# Schema1.net
KiCad netlist of a schematic drawn in Altium Designer
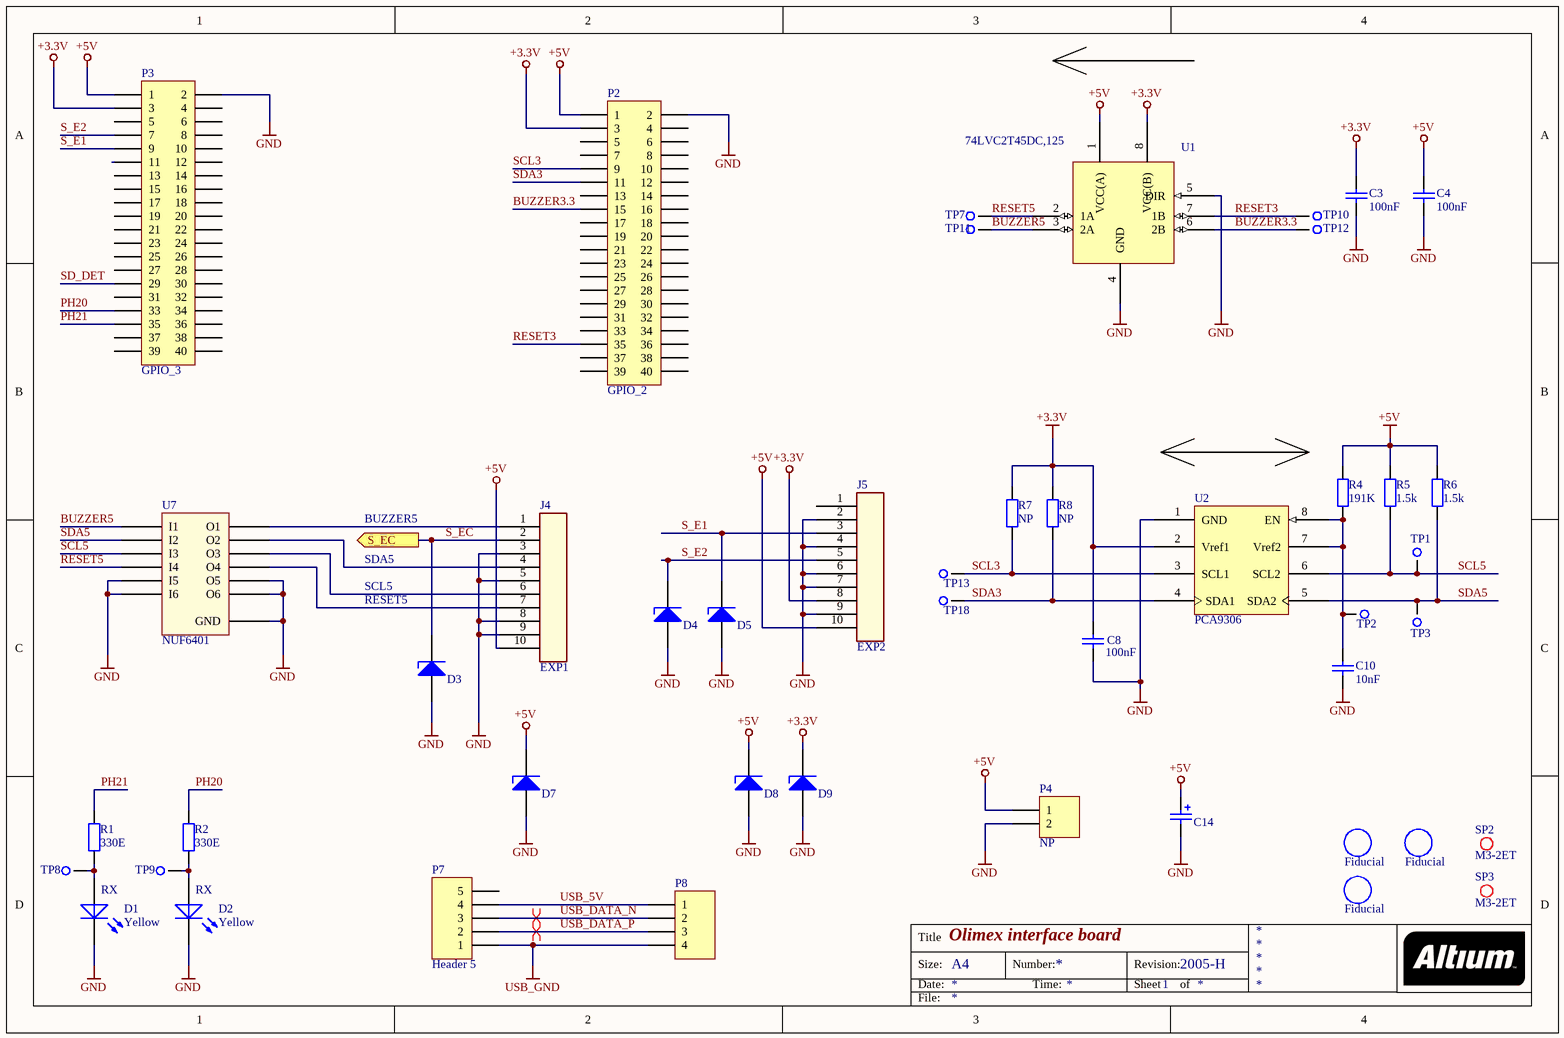
[diagram p0: Schema1.SchDoc]

(export (version "E")
  (design (tool "Eeschema 10.0.6"))
  (components
    (comp (ref "C3")
      (value "100nF")
      (footprint "C0805 (2012)")
      (description "Cap 100nF X7R 0805 10% 100V")
      (fields (field (name "MFG") "AVX"))
      (libsource (lib "Faber_SCH_lib") (part "Cap 100nF X7R 0805"))
    )
    (comp (ref "C4")
      (value "100nF")
      (footprint "C0805 (2012)")
      (description "Cap 100nF X7R 0805 10% 100V")
      (fields (field (name "MFG") "AVX"))
      (libsource (lib "Faber_SCH_lib") (part "Cap 100nF X7R 0805"))
    )
    (comp (ref "C8")
      (value "100nF")
      (footprint "C0805 (2012)")
      (description "Cap 100nF X7R 0805 10% 100V")
      (fields (field (name "MFG") "AVX"))
      (libsource (lib "Faber_SCH_lib") (part "Cap 100nF X7R 0805"))
    )
    (comp (ref "C10")
      (value "10nF")
      (footprint "C0805 (2012)")
      (description "Cap 10nF X7R 0805 10% 100V")
      (fields (field (name "MFG") "AVX"))
      (libsource (lib "Faber_SCH_lib") (part "Cap 10nF X7R 0805"))
    )
    (comp (ref "C14")
      (value "470u")
      (footprint "CAPAE7866X80M")
      (description "CAP ALUM 470UF 20% 10V SMD")
      (fields (field (name "MFG") "Panasonic Electronic Components") (field (name "TOLERANCE") "±20%"))
      (libsource (lib "Olimex interface board") (part "CAP ALUM 470UF 20% 10V SMD"))
    )
    (comp (ref "D1")
      (value "Yellow")
      (footprint "LED0805-YELLOW")
      (description "RO LED GEEL HSMY-C170 0805  AVAGO")
      (fields (field (name "MFG") "AVAGO"))
      (libsource (lib "Database_Faber") (part "LED"))
    )
    (comp (ref "D2")
      (value "Yellow")
      (footprint "LED0805-YELLOW")
      (description "RO LED GEEL HSMY-C170 0805  AVAGO")
      (fields (field (name "MFG") "AVAGO"))
      (libsource (lib "Database_Faber") (part "LED"))
    )
    (comp (ref "D3")
      (value "ESD9X3.3ST5G")
      (footprint "SODFL100X40-2N")
      (description "TVS DIODE 3.3VWM 10.4VC SOD923")
      (fields (field (name "MFG") "ON Semiconductor"))
      (libsource (lib "Olimex interface board") (part "ESD9X3.3ST5G"))
    )
    (comp (ref "D4")
      (value "ESD9X3.3ST5G")
      (footprint "SODFL100X40-2N")
      (description "TVS DIODE 3.3VWM 10.4VC SOD923")
      (fields (field (name "MFG") "ON Semiconductor"))
      (libsource (lib "Olimex interface board") (part "ESD9X3.3ST5G"))
    )
    (comp (ref "D5")
      (value "ESD9X3.3ST5G")
      (footprint "SODFL100X40-2N")
      (description "TVS DIODE 3.3VWM 10.4VC SOD923")
      (fields (field (name "MFG") "ON Semiconductor"))
      (libsource (lib "Olimex interface board") (part "ESD9X3.3ST5G"))
    )
    (comp (ref "D7")
      (value "ESD9X5.0ST5G")
      (footprint "SODFL100X40-2N")
      (description "TVS DIODE 5VWM 12.3VC SOD923")
      (fields (field (name "MFG") "ON Semiconductor"))
      (libsource (lib "Olimex interface board") (part "ESD9X5.0ST5G"))
    )
    (comp (ref "D8")
      (value "ESD9X5.0ST5G")
      (footprint "SODFL100X40-2N")
      (description "TVS DIODE 5VWM 12.3VC SOD923")
      (fields (field (name "MFG") "ON Semiconductor"))
      (libsource (lib "Olimex interface board") (part "ESD9X5.0ST5G"))
    )
    (comp (ref "D9")
      (value "ESD9X3.3ST5G")
      (footprint "SODFL100X40-2N")
      (description "TVS DIODE 3.3VWM 10.4VC SOD923")
      (fields (field (name "MFG") "ON Semiconductor"))
      (libsource (lib "Olimex interface board") (part "ESD9X3.3ST5G"))
    )
    (comp (ref "Fid1")
      (value "Fiducial")
      (footprint "Fiducial 1,5mm")
      (libsource (lib "Database_Faber") (part "Fiducial"))
    )
    (comp (ref "Fid2")
      (value "Fiducial")
      (footprint "Fiducial 1,5mm")
      (libsource (lib "Database_Faber") (part "Fiducial"))
    )
    (comp (ref "Fid3")
      (value "Fiducial")
      (footprint "Fiducial 1,5mm")
      (libsource (lib "Database_Faber") (part "Fiducial"))
    )
    (comp (ref "J4")
      (value "EXP1")
      (footprint "BOXHEADER-10P-R/A-ST-2.54")
      (description "RO CONN PR HDR BOX 10p HKS 61201021721 WUERTH")
      (libsource (lib "Database_Faber") (part "HEADER 10"))
    )
    (comp (ref "J5")
      (value "EXP2")
      (footprint "BOXHEADER-10P-R/A-ST-2.54")
      (description "RO CONN PR HDR BOX 10p HKS 61201021721 WUERTH")
      (libsource (lib "Database_Faber") (part "HEADER 10"))
    )
    (comp (ref "P2")
      (value "GPIO_2")
      (footprint "M50-3152042")
      (description "HARWIN - M50-3152042 - SOCKET, DUAL ENTRY, SMT, 40WAY")
      (fields (field (name "MFG") "Harwin") (field (name "PUBLISHER") "Altium Limited"))
      (libsource (lib "Miscellaneous Connectors") (part "MHDR2X20"))
    )
    (comp (ref "P3")
      (value "GPIO_3")
      (footprint "M50-3152042")
      (description "HARWIN - M50-3152042 - SOCKET, DUAL ENTRY, SMT, 40WAY")
      (fields (field (name "MFG") "Harwin") (field (name "PUBLISHER") "Altium Limited"))
      (libsource (lib "Miscellaneous Connectors") (part "MHDR2X20"))
    )
    (comp (ref "P4")
      (value "NP")
      (footprint "HDR1X2")
      (fields (field (name "PUBLISHER") "Altium Limited"))
      (libsource (lib "Miscellaneous Connectors") (part "Header 2"))
    )
    (comp (ref "P7")
      (value "Header 5")
      (footprint "Female Header 5 pins")
      (description "Header, 5-Pin")
      (fields (field (name "MFG") "Multicomp"))
      (libsource (lib "Miscellaneous Connectors") (part "Header 5"))
    )
    (comp (ref "P8")
      (value "~")
      (footprint "B4B-XH-A")
      (description "Header, 4-Pin")
      (fields
        (field (name "MFG") "JST (JAPAN SOLDERLESS TERMINALS)")
        (field (name "PUBLISHER") "Altium Limited")
      )
      (libsource (lib "Miscellaneous Connectors") (part "Header 4"))
    )
    (comp (ref "R1")
      (value "330E")
      (footprint "RESC1608X05N")
      (description "RES 330 OHM 1/10W 1% 0603 SMD")
      (fields
        (field (name "MANUFACTURER") "Vishay Dale")
        (field (name "MANUFACTURER PART NUMBER") "CRCW0603330RFKEA")
      )
      (libsource (lib "Marlin") (part "330E/0603"))
    )
    (comp (ref "R2")
      (value "330E")
      (footprint "RESC1608X05N")
      (description "RES 330 OHM 1/10W 1% 0603 SMD")
      (fields
        (field (name "MANUFACTURER") "Vishay Dale")
        (field (name "MANUFACTURER PART NUMBER") "CRCW0603330RFKEA")
      )
      (libsource (lib "Marlin") (part "330E/0603"))
    )
    (comp (ref "R4")
      (value "191K")
      (footprint "R0805 (2012)")
      (description "Res 191K 0805 1% 125mW")
      (fields (field (name "MFG") "VISHAY DRALORIC"))
      (libsource (lib "Faber_SCH_lib") (part "Res 191K 0805"))
    )
    (comp (ref "R5")
      (value "1.5k")
      (footprint "RESC1608X05N")
      (description "RES SMD 1.5K OHM 1% 1/10W 0603")
      (fields
        (field (name "MANUFACTURER") "Vishay Dale")
        (field (name "MANUFACTURER PART NUMBER") "CRCW06031K50FKEA")
      )
      (libsource (lib "Olimex interface board") (part "47k/0603"))
    )
    (comp (ref "R6")
      (value "1.5k")
      (footprint "RESC1608X05N")
      (description "RES SMD 1.5K OHM 1% 1/10W 0603")
      (fields
        (field (name "MANUFACTURER") "Vishay Dale")
        (field (name "MANUFACTURER PART NUMBER") "CRCW06031K50FKEA")
      )
      (libsource (lib "Olimex interface board") (part "47k/0603"))
    )
    (comp (ref "R7")
      (value "NP")
      (footprint "R0805 (2012)")
      (description "Res 4.7K 0805 1% 100mW")
      (fields (field (name "MFG") "MULTICOMP"))
      (libsource (lib "Faber_SCH_lib") (part "Res 4.7K 0805"))
    )
    (comp (ref "R8")
      (value "NP")
      (footprint "R0805 (2012)")
      (description "Res 4.7K 0805 1% 100mW")
      (fields (field (name "MFG") "MULTICOMP"))
      (libsource (lib "Faber_SCH_lib") (part "Res 4.7K 0805"))
    )
    (comp (ref "SP2")
      (value "M3-2ET")
      (footprint "SPACER M3-4ET")
      (description "MOER-SMD SMTSO-M3-2ET  PEM")
      (fields (field (name "MFG") "PEM"))
      (libsource (lib "Faber_SCH_lib") (part "Spacer M3-10ET"))
    )
    (comp (ref "SP3")
      (value "M3-2ET")
      (footprint "Spacer M3-4ETkleinepad")
      (description "MOER-SMD SMTSO-M3-2ET  PEM")
      (fields (field (name "MFG") "PEM"))
      (libsource (lib "Faber_SCH_lib") (part "Spacer M3-10ET"))
    )
    (comp (ref "TP1")
      (value "2mm")
      (footprint "TESTPOINT 2mm")
      (description "Testpoint, 2mm, round")
      (libsource (lib "Faber_SCH_lib") (part "Testpoint, 2mm, round"))
    )
    (comp (ref "TP2")
      (value "2mm")
      (footprint "TESTPOINT 2mm")
      (description "Testpoint, 2mm, round")
      (libsource (lib "Faber_SCH_lib") (part "Testpoint, 2mm, round"))
    )
    (comp (ref "TP3")
      (value "2mm")
      (footprint "TESTPOINT 2mm")
      (description "Testpoint, 2mm, round")
      (libsource (lib "Faber_SCH_lib") (part "Testpoint, 2mm, round"))
    )
    (comp (ref "TP7")
      (value "2mm")
      (footprint "TESTPOINT 2mm")
      (description "Testpoint, 2mm, round")
      (libsource (lib "Faber_SCH_lib") (part "Testpoint, 2mm, round"))
    )
    (comp (ref "TP8")
      (value "2mm")
      (footprint "TESTPOINT 2mm")
      (description "Testpoint, 2mm, round")
      (libsource (lib "Faber_SCH_lib") (part "Testpoint, 2mm, round"))
    )
    (comp (ref "TP9")
      (value "2mm")
      (footprint "TESTPOINT 2mm")
      (description "Testpoint, 2mm, round")
      (libsource (lib "Faber_SCH_lib") (part "Testpoint, 2mm, round"))
    )
    (comp (ref "TP10")
      (value "2mm")
      (footprint "TESTPOINT 2mm")
      (description "Testpoint, 2mm, round")
      (libsource (lib "Faber_SCH_lib") (part "Testpoint, 2mm, round"))
    )
    (comp (ref "TP11")
      (value "2mm")
      (footprint "TESTPOINT 2mm")
      (description "Testpoint, 2mm, round")
      (libsource (lib "Faber_SCH_lib") (part "Testpoint, 2mm, round"))
    )
    (comp (ref "TP12")
      (value "2mm")
      (footprint "TESTPOINT 2mm")
      (description "Testpoint, 2mm, round")
      (libsource (lib "Faber_SCH_lib") (part "Testpoint, 2mm, round"))
    )
    (comp (ref "TP13")
      (value "2mm")
      (footprint "TESTPOINT 2mm")
      (description "Testpoint, 2mm, round")
      (libsource (lib "Faber_SCH_lib") (part "Testpoint, 2mm, round"))
    )
    (comp (ref "TP18")
      (value "2mm")
      (footprint "TESTPOINT 2mm")
      (description "Testpoint, 2mm, round")
      (libsource (lib "Faber_SCH_lib") (part "Testpoint, 2mm, round"))
    )
    (comp (ref "U1")
      (value "74LVC2T45DC,125")
      (footprint "TSSOP50P310X100-8N")
      (description "2-bit translaing transceiver")
      (fields (field (name "MFG") "NXP"))
      (libsource (lib "Olimex interface board") (part "74LVC2T45DC,125"))
    )
    (comp (ref "U2")
      (value "PCA9306")
      (footprint "IC SSOP-8")
      (description "IC PCA9306 Voltage Level translator")
      (fields (field (name "MFG") "TEXAS INSTRUMENTS"))
      (libsource (lib "Faber_SCH_lib") (part "IC PCA9306"))
    )
    (comp (ref "U7")
      (value "NUF6401")
      (footprint "SON50P140X100_HS-13N")
      (fields (field (name "MFG") "ON Semiconductor"))
      (libsource (lib "UltiController") (part "NUF6401"))
    )
  )
  (nets
    (net (code "1") (name "+3.3V") (class "Default")
      (node (ref "C3") (pin "1") (pinfunction "1_1") (pintype "passive"))
      (node (ref "C8") (pin "2") (pinfunction "2_2") (pintype "passive"))
      (node (ref "D9") (pin "1") (pinfunction "K_1") (pintype "passive"))
      (node (ref "J5") (pin "8") (pinfunction "8_8") (pintype "passive"))
      (node (ref "P2") (pin "3") (pinfunction "3_3") (pintype "passive"))
      (node (ref "P3") (pin "3") (pinfunction "3_3") (pintype "passive"))
      (node (ref "R7") (pin "2") (pinfunction "2_2") (pintype "passive"))
      (node (ref "R8") (pin "2") (pinfunction "2_2") (pintype "passive"))
      (node (ref "U1") (pin "8") (pinfunction "VCC(B)_8") (pintype "power_in"))
      (node (ref "U2") (pin "2") (pinfunction "Vref1_2") (pintype "power_in"))
    )
    (net (code "2") (name "+5V") (class "Default")
      (node (ref "C14") (pin "1") (pinfunction "1_1") (pintype "passive"))
      (node (ref "C4") (pin "1") (pinfunction "1_1") (pintype "passive"))
      (node (ref "D7") (pin "1") (pinfunction "K_1") (pintype "passive"))
      (node (ref "D8") (pin "1") (pinfunction "K_1") (pintype "passive"))
      (node (ref "J4") (pin "10") (pinfunction "10_10") (pintype "passive"))
      (node (ref "J5") (pin "10") (pinfunction "10_10") (pintype "passive"))
      (node (ref "P2") (pin "1") (pinfunction "1_1") (pintype "passive"))
      (node (ref "P3") (pin "1") (pinfunction "1_1") (pintype "passive"))
      (node (ref "P4") (pin "1") (pinfunction "1_1") (pintype "passive"))
      (node (ref "R4") (pin "2") (pinfunction "2_2") (pintype "passive"))
      (node (ref "R5") (pin "2") (pinfunction "2_2") (pintype "passive"))
      (node (ref "R6") (pin "2") (pinfunction "2_2") (pintype "passive"))
      (node (ref "U1") (pin "1") (pinfunction "VCC(A)_1") (pintype "power_in"))
    )
    (net (code "3") (name "/BUZZER3.3") (class "Default")
      (node (ref "P2") (pin "15") (pinfunction "15_15") (pintype "passive"))
      (node (ref "TP12") (pin "1") (pinfunction "1_1") (pintype "passive"))
      (node (ref "U1") (pin "6") (pinfunction "2B_6") (pintype "bidirectional"))
    )
    (net (code "4") (name "/BUZZER5") (class "Default")
      (node (ref "TP11") (pin "1") (pinfunction "1_1") (pintype "passive"))
      (node (ref "U1") (pin "3") (pinfunction "2A_3") (pintype "bidirectional"))
      (node (ref "U7") (pin "1") (pinfunction "I1_1") (pintype "passive"))
    )
    (net (code "5") (name "/PH20") (class "Default")
      (node (ref "P3") (pin "33") (pinfunction "33_33") (pintype "passive"))
      (node (ref "R2") (pin "2") (pinfunction "2_2") (pintype "passive"))
    )
    (net (code "6") (name "/PH21") (class "Default")
      (node (ref "P3") (pin "35") (pinfunction "35_35") (pintype "passive"))
      (node (ref "R1") (pin "2") (pinfunction "2_2") (pintype "passive"))
    )
    (net (code "7") (name "/RESET3") (class "Default")
      (node (ref "P2") (pin "35") (pinfunction "35_35") (pintype "passive"))
      (node (ref "TP10") (pin "1") (pinfunction "1_1") (pintype "passive"))
      (node (ref "U1") (pin "7") (pinfunction "1B_7") (pintype "bidirectional"))
    )
    (net (code "8") (name "/RESET5") (class "Default")
      (node (ref "TP7") (pin "1") (pinfunction "1_1") (pintype "passive"))
      (node (ref "U1") (pin "2") (pinfunction "1A_2") (pintype "bidirectional"))
      (node (ref "U7") (pin "4") (pinfunction "I4_4") (pintype "passive"))
    )
    (net (code "9") (name "/SCL3") (class "Default")
      (node (ref "P2") (pin "9") (pinfunction "9_9") (pintype "passive"))
      (node (ref "R7") (pin "1") (pinfunction "1_1") (pintype "passive"))
      (node (ref "TP13") (pin "1") (pinfunction "1_1") (pintype "passive"))
      (node (ref "U2") (pin "3") (pinfunction "SCL1_3") (pintype "passive"))
    )
    (net (code "10") (name "/SCL5") (class "Default")
      (node (ref "R5") (pin "1") (pinfunction "1_1") (pintype "passive"))
      (node (ref "TP1") (pin "1") (pinfunction "1_1") (pintype "passive"))
      (node (ref "U2") (pin "6") (pinfunction "SCL2_6") (pintype "passive"))
      (node (ref "U7") (pin "3") (pinfunction "I3_3") (pintype "passive"))
    )
    (net (code "11") (name "/SDA3") (class "Default")
      (node (ref "P2") (pin "11") (pinfunction "11_11") (pintype "passive"))
      (node (ref "R8") (pin "1") (pinfunction "1_1") (pintype "passive"))
      (node (ref "TP18") (pin "1") (pinfunction "1_1") (pintype "passive"))
      (node (ref "U2") (pin "4") (pinfunction "SDA1_4") (pintype "passive"))
    )
    (net (code "12") (name "/SDA5") (class "Default")
      (node (ref "R6") (pin "1") (pinfunction "1_1") (pintype "passive"))
      (node (ref "TP3") (pin "1") (pinfunction "1_1") (pintype "passive"))
      (node (ref "U2") (pin "5") (pinfunction "SDA2_5") (pintype "passive"))
      (node (ref "U7") (pin "2") (pinfunction "I2_2") (pintype "passive"))
    )
    (net (code "13") (name "/SD_DET") (class "Default")
      (node (ref "P3") (pin "29") (pinfunction "29_29") (pintype "passive"))
    )
    (net (code "14") (name "/S_E1") (class "Default")
      (node (ref "D5") (pin "1") (pinfunction "K_1") (pintype "passive"))
      (node (ref "J5") (pin "3") (pinfunction "3_3") (pintype "passive"))
      (node (ref "P3") (pin "9") (pinfunction "9_9") (pintype "passive"))
    )
    (net (code "15") (name "/S_E2") (class "Default")
      (node (ref "D4") (pin "1") (pinfunction "K_1") (pintype "passive"))
      (node (ref "J5") (pin "5") (pinfunction "5_5") (pintype "passive"))
      (node (ref "P3") (pin "7") (pinfunction "7_7") (pintype "passive"))
    )
    (net (code "16") (name "/S_EC") (class "Default")
      (node (ref "D3") (pin "1") (pinfunction "K_1") (pintype "passive"))
      (node (ref "J4") (pin "2") (pinfunction "2_2") (pintype "passive"))
    )
    (net (code "17") (name "/USB_5V") (class "Default")
      (node (ref "P7") (pin "4") (pinfunction "4_4") (pintype "passive"))
      (node (ref "P8") (pin "1") (pinfunction "1_1") (pintype "passive"))
    )
    (net (code "18") (name "/USB_DATA_N") (class "Default")
      (node (ref "P7") (pin "3") (pinfunction "3_3") (pintype "passive"))
      (node (ref "P8") (pin "2") (pinfunction "2_2") (pintype "passive"))
    )
    (net (code "19") (name "/USB_DATA_P") (class "Default")
      (node (ref "P7") (pin "2") (pinfunction "2_2") (pintype "passive"))
      (node (ref "P8") (pin "3") (pinfunction "3_3") (pintype "passive"))
    )
    (net (code "20") (name "GND") (class "Default")
      (node (ref "C10") (pin "1") (pinfunction "1_1") (pintype "passive"))
      (node (ref "C14") (pin "2") (pinfunction "2_2") (pintype "passive"))
      (node (ref "C3") (pin "2") (pinfunction "2_2") (pintype "passive"))
      (node (ref "C4") (pin "2") (pinfunction "2_2") (pintype "passive"))
      (node (ref "C8") (pin "1") (pinfunction "1_1") (pintype "passive"))
      (node (ref "D1") (pin "2") (pinfunction "K_2") (pintype "passive"))
      (node (ref "D2") (pin "2") (pinfunction "K_2") (pintype "passive"))
      (node (ref "D3") (pin "2") (pinfunction "A_2") (pintype "passive"))
      (node (ref "D4") (pin "2") (pinfunction "A_2") (pintype "passive"))
      (node (ref "D5") (pin "2") (pinfunction "A_2") (pintype "passive"))
      (node (ref "D7") (pin "2") (pinfunction "A_2") (pintype "passive"))
      (node (ref "D8") (pin "2") (pinfunction "A_2") (pintype "passive"))
      (node (ref "D9") (pin "2") (pinfunction "A_2") (pintype "passive"))
      (node (ref "J4") (pin "3") (pinfunction "3_3") (pintype "passive"))
      (node (ref "J4") (pin "5") (pinfunction "5_5") (pintype "passive"))
      (node (ref "J4") (pin "8") (pinfunction "8_8") (pintype "passive"))
      (node (ref "J4") (pin "9") (pinfunction "9_9") (pintype "passive"))
      (node (ref "J5") (pin "2") (pinfunction "2_2") (pintype "passive"))
      (node (ref "J5") (pin "4") (pinfunction "4_4") (pintype "passive"))
      (node (ref "J5") (pin "6") (pinfunction "6_6") (pintype "passive"))
      (node (ref "J5") (pin "7") (pinfunction "7_7") (pintype "passive"))
      (node (ref "J5") (pin "9") (pinfunction "9_9") (pintype "passive"))
      (node (ref "P2") (pin "2") (pinfunction "2_2") (pintype "passive"))
      (node (ref "P3") (pin "2") (pinfunction "2_2") (pintype "passive"))
      (node (ref "P4") (pin "2") (pinfunction "2_2") (pintype "passive"))
      (node (ref "U1") (pin "4") (pinfunction "GND_4") (pintype "power_in"))
      (node (ref "U1") (pin "5") (pinfunction "DIR_5") (pintype "input"))
      (node (ref "U2") (pin "1") (pinfunction "GND_1") (pintype "power_in"))
      (node (ref "U7") (pin "13") (pinfunction "GND_13") (pintype "passive"))
      (node (ref "U7") (pin "5") (pinfunction "I5_5") (pintype "passive"))
      (node (ref "U7") (pin "6") (pinfunction "I6_6") (pintype "passive"))
      (node (ref "U7") (pin "7") (pinfunction "O6_7") (pintype "passive"))
      (node (ref "U7") (pin "8") (pinfunction "O5_8") (pintype "passive"))
    )
    (net (code "21") (name "Net-(D1-A)") (class "Default")
      (node (ref "D1") (pin "1") (pinfunction "A_1") (pintype "passive"))
      (node (ref "R1") (pin "1") (pinfunction "1_1") (pintype "passive"))
      (node (ref "TP8") (pin "1") (pinfunction "1_1") (pintype "passive"))
    )
    (net (code "22") (name "Net-(D2-A)") (class "Default")
      (node (ref "D2") (pin "1") (pinfunction "A_1") (pintype "passive"))
      (node (ref "R2") (pin "1") (pinfunction "1_1") (pintype "passive"))
      (node (ref "TP9") (pin "1") (pinfunction "1_1") (pintype "passive"))
    )
    (net (code "23") (name "Net-(U2-EN)") (class "Default")
      (node (ref "C10") (pin "2") (pinfunction "2_2") (pintype "passive"))
      (node (ref "R4") (pin "1") (pinfunction "1_1") (pintype "passive"))
      (node (ref "TP2") (pin "1") (pinfunction "1_1") (pintype "passive"))
      (node (ref "U2") (pin "7") (pinfunction "Vref2_7") (pintype "power_in"))
      (node (ref "U2") (pin "8") (pinfunction "EN_8") (pintype "input"))
    )
    (net (code "24") (name "Net-(U7-O1)") (class "Default")
      (node (ref "J4") (pin "1") (pinfunction "1_1") (pintype "passive"))
      (node (ref "U7") (pin "12") (pinfunction "O1_12") (pintype "passive"))
    )
    (net (code "25") (name "Net-(U7-O2)") (class "Default")
      (node (ref "J4") (pin "4") (pinfunction "4_4") (pintype "passive"))
      (node (ref "U7") (pin "11") (pinfunction "O2_11") (pintype "passive"))
    )
    (net (code "26") (name "Net-(U7-O3)") (class "Default")
      (node (ref "J4") (pin "6") (pinfunction "6_6") (pintype "passive"))
      (node (ref "U7") (pin "10") (pinfunction "O3_10") (pintype "passive"))
    )
    (net (code "27") (name "Net-(U7-O4)") (class "Default")
      (node (ref "J4") (pin "7") (pinfunction "7_7") (pintype "passive"))
      (node (ref "U7") (pin "9") (pinfunction "O4_9") (pintype "passive"))
    )
    (net (code "28") (name "USB_GND") (class "Default")
      (node (ref "P7") (pin "1") (pinfunction "1_1") (pintype "passive"))
      (node (ref "P8") (pin "4") (pinfunction "4_4") (pintype "passive"))
    )
    (net (code "29") (name "unconnected-(J5-Pad1)") (class "Default")
      (node (ref "J5") (pin "1") (pinfunction "1_1") (pintype "passive"))
    )
    (net (code "30") (name "unconnected-(P2-Pad4)") (class "Default")
      (node (ref "P2") (pin "4") (pinfunction "4_4") (pintype "passive"))
    )
    (net (code "31") (name "unconnected-(P2-Pad5)") (class "Default")
      (node (ref "P2") (pin "5") (pinfunction "5_5") (pintype "passive"))
    )
    (net (code "32") (name "unconnected-(P2-Pad6)") (class "Default")
      (node (ref "P2") (pin "6") (pinfunction "6_6") (pintype "passive"))
    )
    (net (code "33") (name "unconnected-(P2-Pad7)") (class "Default")
      (node (ref "P2") (pin "7") (pinfunction "7_7") (pintype "passive"))
    )
    (net (code "34") (name "unconnected-(P2-Pad8)") (class "Default")
      (node (ref "P2") (pin "8") (pinfunction "8_8") (pintype "passive"))
    )
    (net (code "35") (name "unconnected-(P2-Pad10)") (class "Default")
      (node (ref "P2") (pin "10") (pinfunction "10_10") (pintype "passive"))
    )
    (net (code "36") (name "unconnected-(P2-Pad12)") (class "Default")
      (node (ref "P2") (pin "12") (pinfunction "12_12") (pintype "passive"))
    )
    (net (code "37") (name "unconnected-(P2-Pad13)") (class "Default")
      (node (ref "P2") (pin "13") (pinfunction "13_13") (pintype "passive"))
    )
    (net (code "38") (name "unconnected-(P2-Pad14)") (class "Default")
      (node (ref "P2") (pin "14") (pinfunction "14_14") (pintype "passive"))
    )
    (net (code "39") (name "unconnected-(P2-Pad16)") (class "Default")
      (node (ref "P2") (pin "16") (pinfunction "16_16") (pintype "passive"))
    )
    (net (code "40") (name "unconnected-(P2-Pad17)") (class "Default")
      (node (ref "P2") (pin "17") (pinfunction "17_17") (pintype "passive"))
    )
    (net (code "41") (name "unconnected-(P2-Pad18)") (class "Default")
      (node (ref "P2") (pin "18") (pinfunction "18_18") (pintype "passive"))
    )
    (net (code "42") (name "unconnected-(P2-Pad19)") (class "Default")
      (node (ref "P2") (pin "19") (pinfunction "19_19") (pintype "passive"))
    )
    (net (code "43") (name "unconnected-(P2-Pad20)") (class "Default")
      (node (ref "P2") (pin "20") (pinfunction "20_20") (pintype "passive"))
    )
    (net (code "44") (name "unconnected-(P2-Pad21)") (class "Default")
      (node (ref "P2") (pin "21") (pinfunction "21_21") (pintype "passive"))
    )
    (net (code "45") (name "unconnected-(P2-Pad22)") (class "Default")
      (node (ref "P2") (pin "22") (pinfunction "22_22") (pintype "passive"))
    )
    (net (code "46") (name "unconnected-(P2-Pad23)") (class "Default")
      (node (ref "P2") (pin "23") (pinfunction "23_23") (pintype "passive"))
    )
    (net (code "47") (name "unconnected-(P2-Pad24)") (class "Default")
      (node (ref "P2") (pin "24") (pinfunction "24_24") (pintype "passive"))
    )
    (net (code "48") (name "unconnected-(P2-Pad25)") (class "Default")
      (node (ref "P2") (pin "25") (pinfunction "25_25") (pintype "passive"))
    )
    (net (code "49") (name "unconnected-(P2-Pad26)") (class "Default")
      (node (ref "P2") (pin "26") (pinfunction "26_26") (pintype "passive"))
    )
    (net (code "50") (name "unconnected-(P2-Pad27)") (class "Default")
      (node (ref "P2") (pin "27") (pinfunction "27_27") (pintype "passive"))
    )
    (net (code "51") (name "unconnected-(P2-Pad28)") (class "Default")
      (node (ref "P2") (pin "28") (pinfunction "28_28") (pintype "passive"))
    )
    (net (code "52") (name "unconnected-(P2-Pad29)") (class "Default")
      (node (ref "P2") (pin "29") (pinfunction "29_29") (pintype "passive"))
    )
    (net (code "53") (name "unconnected-(P2-Pad30)") (class "Default")
      (node (ref "P2") (pin "30") (pinfunction "30_30") (pintype "passive"))
    )
    (net (code "54") (name "unconnected-(P2-Pad31)") (class "Default")
      (node (ref "P2") (pin "31") (pinfunction "31_31") (pintype "passive"))
    )
    (net (code "55") (name "unconnected-(P2-Pad32)") (class "Default")
      (node (ref "P2") (pin "32") (pinfunction "32_32") (pintype "passive"))
    )
    (net (code "56") (name "unconnected-(P2-Pad33)") (class "Default")
      (node (ref "P2") (pin "33") (pinfunction "33_33") (pintype "passive"))
    )
    (net (code "57") (name "unconnected-(P2-Pad34)") (class "Default")
      (node (ref "P2") (pin "34") (pinfunction "34_34") (pintype "passive"))
    )
    (net (code "58") (name "unconnected-(P2-Pad36)") (class "Default")
      (node (ref "P2") (pin "36") (pinfunction "36_36") (pintype "passive"))
    )
    (net (code "59") (name "unconnected-(P2-Pad37)") (class "Default")
      (node (ref "P2") (pin "37") (pinfunction "37_37") (pintype "passive"))
    )
    (net (code "60") (name "unconnected-(P2-Pad38)") (class "Default")
      (node (ref "P2") (pin "38") (pinfunction "38_38") (pintype "passive"))
    )
    (net (code "61") (name "unconnected-(P2-Pad39)") (class "Default")
      (node (ref "P2") (pin "39") (pinfunction "39_39") (pintype "passive"))
    )
    (net (code "62") (name "unconnected-(P2-Pad40)") (class "Default")
      (node (ref "P2") (pin "40") (pinfunction "40_40") (pintype "passive"))
    )
    (net (code "63") (name "unconnected-(P3-Pad4)") (class "Default")
      (node (ref "P3") (pin "4") (pinfunction "4_4") (pintype "passive"))
    )
    (net (code "64") (name "unconnected-(P3-Pad5)") (class "Default")
      (node (ref "P3") (pin "5") (pinfunction "5_5") (pintype "passive"))
    )
    (net (code "65") (name "unconnected-(P3-Pad6)") (class "Default")
      (node (ref "P3") (pin "6") (pinfunction "6_6") (pintype "passive"))
    )
    (net (code "66") (name "unconnected-(P3-Pad8)") (class "Default")
      (node (ref "P3") (pin "8") (pinfunction "8_8") (pintype "passive"))
    )
    (net (code "67") (name "unconnected-(P3-Pad10)") (class "Default")
      (node (ref "P3") (pin "10") (pinfunction "10_10") (pintype "passive"))
    )
    (net (code "68") (name "unconnected-(P3-Pad11)") (class "Default")
      (node (ref "P3") (pin "11") (pinfunction "11_11") (pintype "passive"))
    )
    (net (code "69") (name "unconnected-(P3-Pad12)") (class "Default")
      (node (ref "P3") (pin "12") (pinfunction "12_12") (pintype "passive"))
    )
    (net (code "70") (name "unconnected-(P3-Pad13)") (class "Default")
      (node (ref "P3") (pin "13") (pinfunction "13_13") (pintype "passive"))
    )
    (net (code "71") (name "unconnected-(P3-Pad14)") (class "Default")
      (node (ref "P3") (pin "14") (pinfunction "14_14") (pintype "passive"))
    )
    (net (code "72") (name "unconnected-(P3-Pad15)") (class "Default")
      (node (ref "P3") (pin "15") (pinfunction "15_15") (pintype "passive"))
    )
    (net (code "73") (name "unconnected-(P3-Pad16)") (class "Default")
      (node (ref "P3") (pin "16") (pinfunction "16_16") (pintype "passive"))
    )
    (net (code "74") (name "unconnected-(P3-Pad17)") (class "Default")
      (node (ref "P3") (pin "17") (pinfunction "17_17") (pintype "passive"))
    )
    (net (code "75") (name "unconnected-(P3-Pad18)") (class "Default")
      (node (ref "P3") (pin "18") (pinfunction "18_18") (pintype "passive"))
    )
    (net (code "76") (name "unconnected-(P3-Pad19)") (class "Default")
      (node (ref "P3") (pin "19") (pinfunction "19_19") (pintype "passive"))
    )
    (net (code "77") (name "unconnected-(P3-Pad20)") (class "Default")
      (node (ref "P3") (pin "20") (pinfunction "20_20") (pintype "passive"))
    )
    (net (code "78") (name "unconnected-(P3-Pad21)") (class "Default")
      (node (ref "P3") (pin "21") (pinfunction "21_21") (pintype "passive"))
    )
    (net (code "79") (name "unconnected-(P3-Pad22)") (class "Default")
      (node (ref "P3") (pin "22") (pinfunction "22_22") (pintype "passive"))
    )
    (net (code "80") (name "unconnected-(P3-Pad23)") (class "Default")
      (node (ref "P3") (pin "23") (pinfunction "23_23") (pintype "passive"))
    )
    (net (code "81") (name "unconnected-(P3-Pad24)") (class "Default")
      (node (ref "P3") (pin "24") (pinfunction "24_24") (pintype "passive"))
    )
    (net (code "82") (name "unconnected-(P3-Pad25)") (class "Default")
      (node (ref "P3") (pin "25") (pinfunction "25_25") (pintype "passive"))
    )
    (net (code "83") (name "unconnected-(P3-Pad26)") (class "Default")
      (node (ref "P3") (pin "26") (pinfunction "26_26") (pintype "passive"))
    )
    (net (code "84") (name "unconnected-(P3-Pad27)") (class "Default")
      (node (ref "P3") (pin "27") (pinfunction "27_27") (pintype "passive"))
    )
    (net (code "85") (name "unconnected-(P3-Pad28)") (class "Default")
      (node (ref "P3") (pin "28") (pinfunction "28_28") (pintype "passive"))
    )
    (net (code "86") (name "unconnected-(P3-Pad30)") (class "Default")
      (node (ref "P3") (pin "30") (pinfunction "30_30") (pintype "passive"))
    )
    (net (code "87") (name "unconnected-(P3-Pad31)") (class "Default")
      (node (ref "P3") (pin "31") (pinfunction "31_31") (pintype "passive"))
    )
    (net (code "88") (name "unconnected-(P3-Pad32)") (class "Default")
      (node (ref "P3") (pin "32") (pinfunction "32_32") (pintype "passive"))
    )
    (net (code "89") (name "unconnected-(P3-Pad34)") (class "Default")
      (node (ref "P3") (pin "34") (pinfunction "34_34") (pintype "passive"))
    )
    (net (code "90") (name "unconnected-(P3-Pad36)") (class "Default")
      (node (ref "P3") (pin "36") (pinfunction "36_36") (pintype "passive"))
    )
    (net (code "91") (name "unconnected-(P3-Pad37)") (class "Default")
      (node (ref "P3") (pin "37") (pinfunction "37_37") (pintype "passive"))
    )
    (net (code "92") (name "unconnected-(P3-Pad38)") (class "Default")
      (node (ref "P3") (pin "38") (pinfunction "38_38") (pintype "passive"))
    )
    (net (code "93") (name "unconnected-(P3-Pad39)") (class "Default")
      (node (ref "P3") (pin "39") (pinfunction "39_39") (pintype "passive"))
    )
    (net (code "94") (name "unconnected-(P3-Pad40)") (class "Default")
      (node (ref "P3") (pin "40") (pinfunction "40_40") (pintype "passive"))
    )
    (net (code "95") (name "unconnected-(P7-Pad5)") (class "Default")
      (node (ref "P7") (pin "5") (pinfunction "5_5") (pintype "passive"))
    )
  )
)
